# ISL.net
KiCad netlist of a schematic drawn in EasyEDA
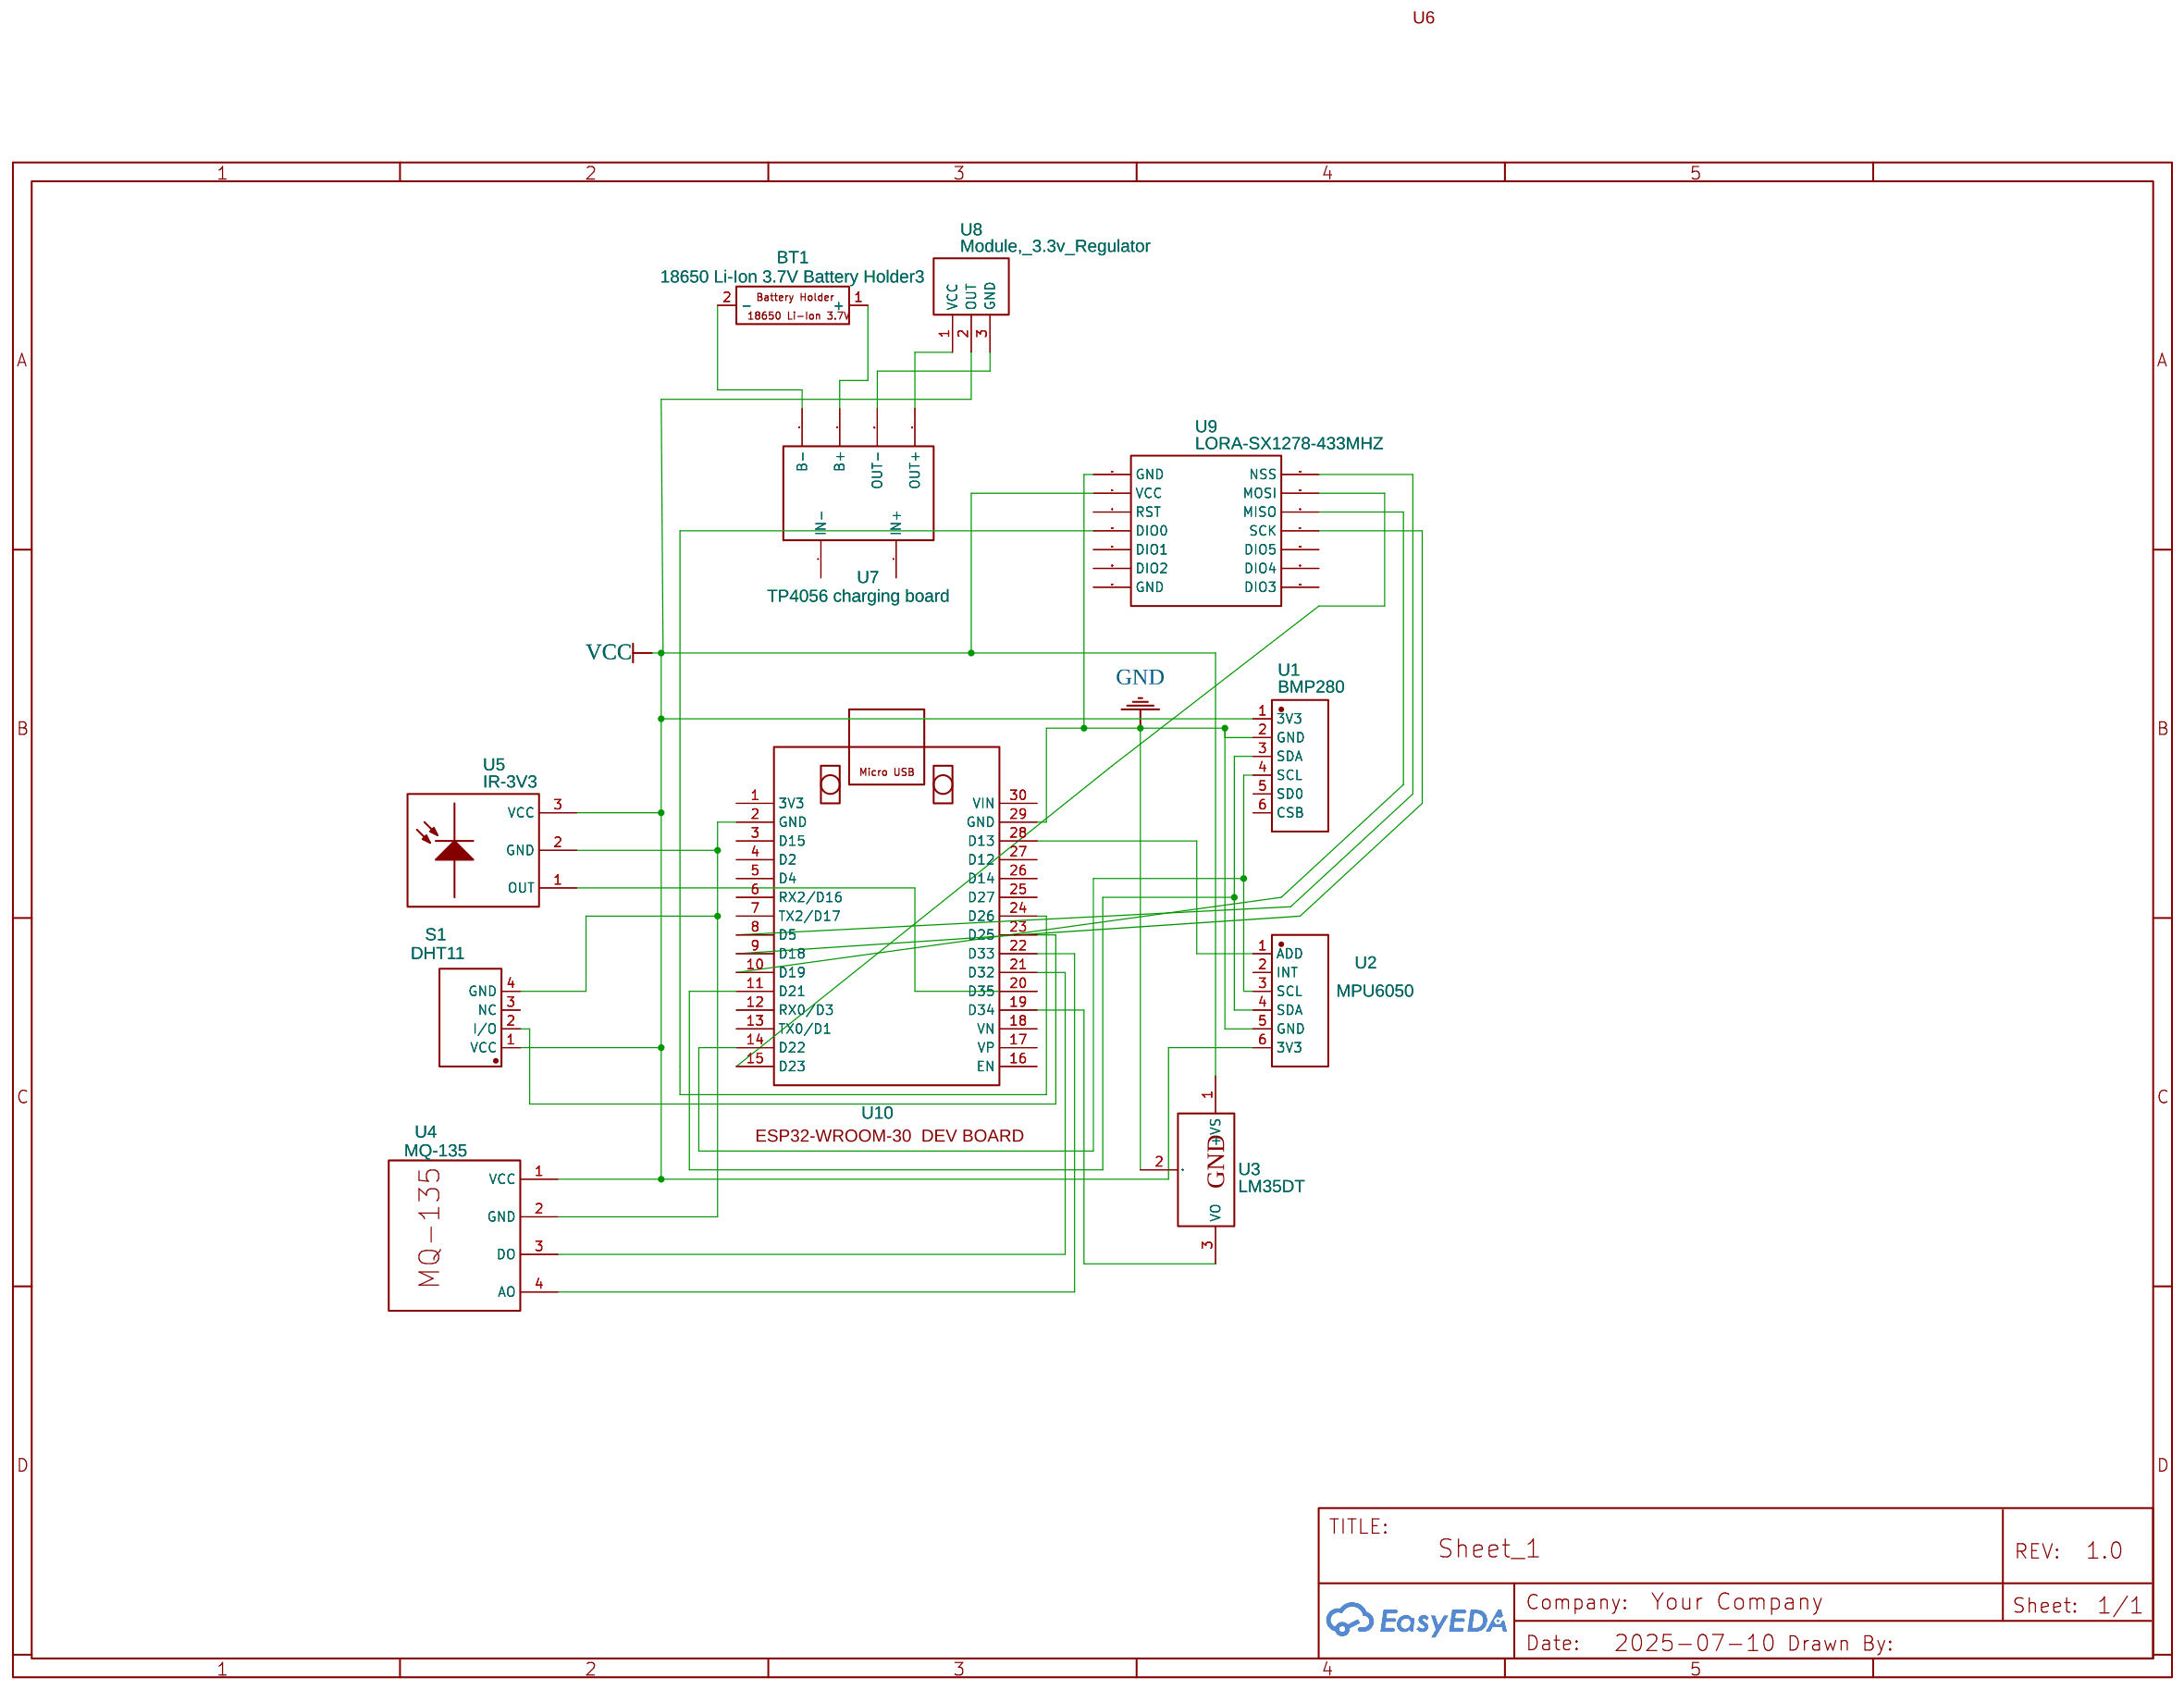
[diagram p0: Sheet_1]
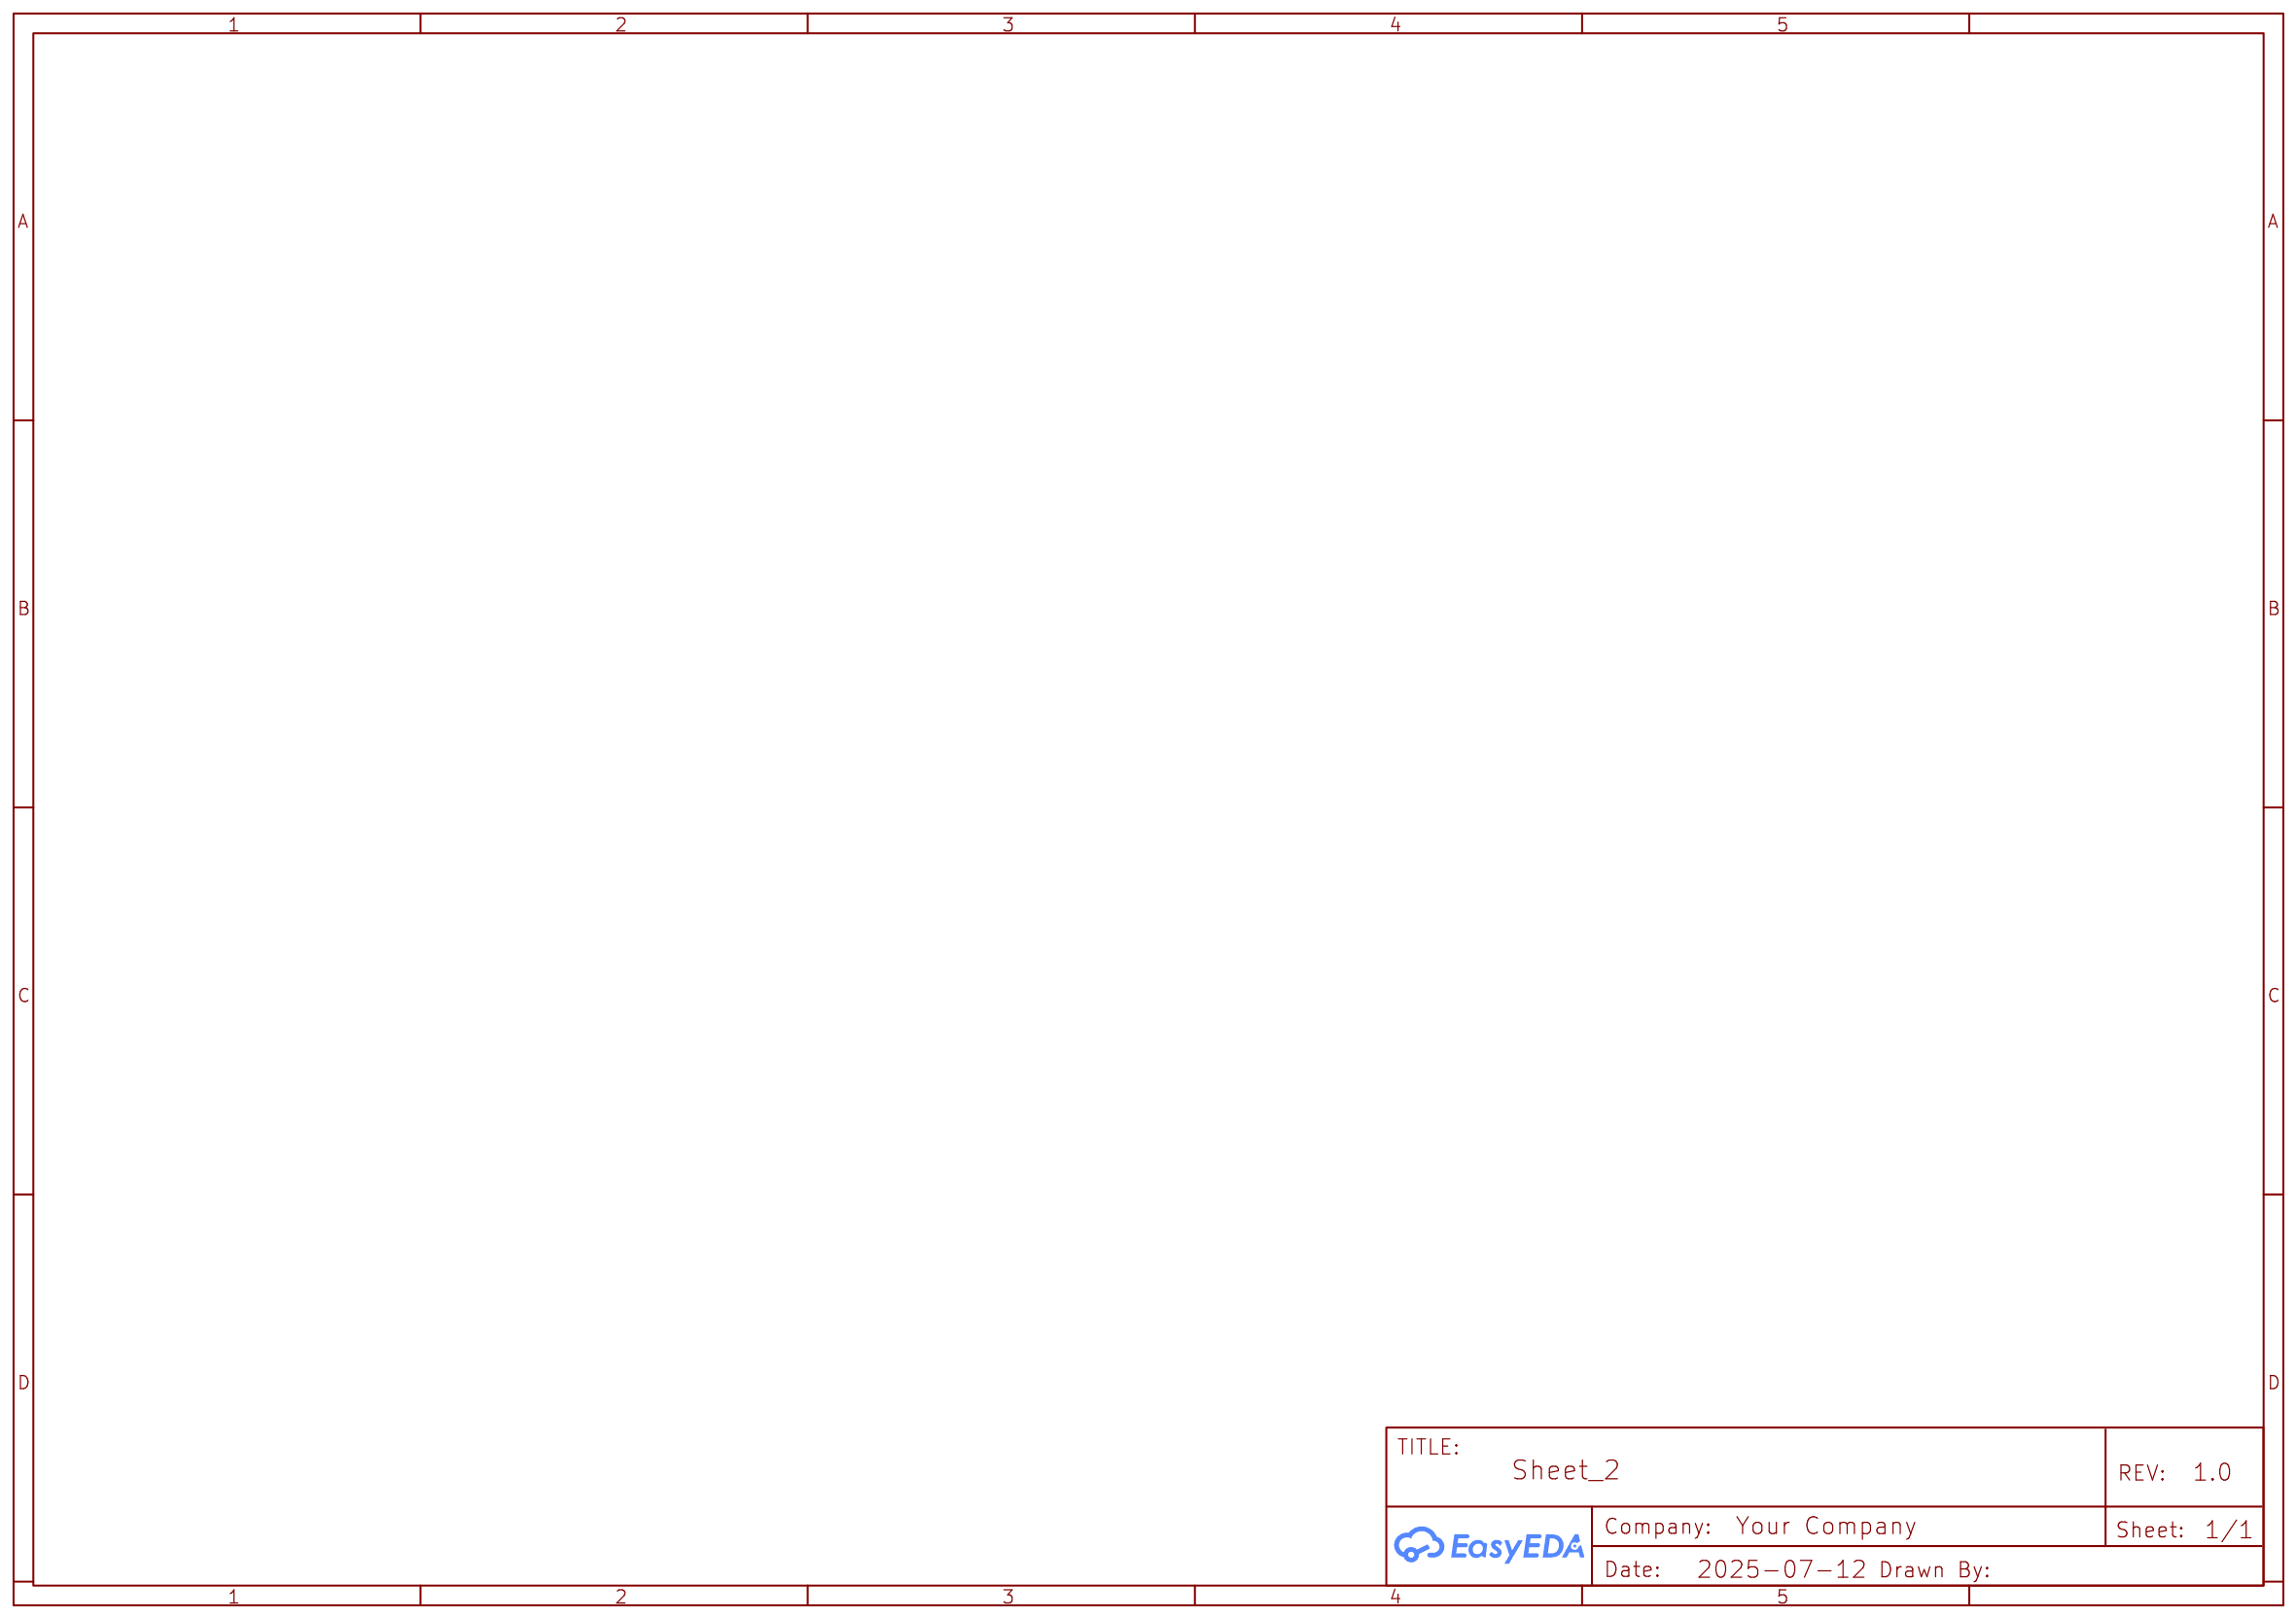
[diagram p1: Sheet_2]

(export (version "E")
  (design (tool "Eeschema 10.0.6"))
  (components
    (comp (ref "BT1")
      (value "18650 Li-Ion 3.7V Battery Holder3")
      (fields (field (name "Manufacturer Part") "18650_Li_BT_3P7V") (field (name "Manufacturer") "Smartcube"))
      (libsource (lib "") (part "18650 Li-Ion 3.7V Battery Holder3"))
    )
    (comp (ref "S1")
      (value "DHT11")
      (fields (field (name "Manufacturer") "AOSONG"))
      (libsource (lib "") (part "DHT11_C87032"))
    )
    (comp (ref "U1") (value "BMP280") (libsource (lib "") (part "BMP280_C9900132626")))
    (comp (ref "U2")
      (value "MPU6050")
      (fields (field (name "Manufacturer Part") "MPU6050-TH"))
      (libsource (lib "") (part "MPU6050-TH"))
    )
    (comp (ref "U3")
      (value "LM35DT")
      (fields (field (name "Manufacturer Part") "LM35DT/NOPB") (field (name "Manufacturer") "TI(德州仪器)"))
      (libsource (lib "") (part "LM35DT"))
    )
    (comp (ref "U4") (value "MQ-135") (libsource (lib "") (part "MQ-135 SENSOR COPY")))
    (comp (ref "U5") (value "IR-3V3") (libsource (lib "") (part "IR-3V3")))
    (comp (ref "U7") (value "TP4056 charging board") (libsource (lib "") (part "TP4056 charging board")))
    (comp (ref "U8")
      (value "Module,_3.3v_Regulator")
      (fields (field (name "Manufacturer Part") "Module, 3.3v Regulator"))
      (libsource (lib "") (part "Module,_3.3v_Regulator"))
    )
    (comp (ref "U9")
      (value "LORA-SX1278-433MHZ")
      (fields (field (name "Manufacturer Part") "New SchematicLib"))
      (libsource (lib "") (part "LORA-SX1278-433MHZ"))
    )
    (comp (ref "U10") (value "ESP32-WROOM-30  DEVB") (libsource (lib "") (part "ESP32-WROOM-30  DEVB")))
  )
  (nets
    (net (code "1") (name "GND") (class "Default")
      (node (ref "U1") (pin "2") (pinfunction "GND_2") (pintype "unspecified"))
      (node (ref "U10") (pin "29") (pinfunction "GND_29") (pintype "unspecified"))
      (node (ref "U2") (pin "5") (pinfunction "GND_5") (pintype "unspecified"))
      (node (ref "U3") (pin "2") (pinfunction "GND_2") (pintype "passive"))
      (node (ref "U9") (pin "GND") (pinfunction "GND_GND") (pintype "unspecified"))
    )
    (net (code "2") (name "Net-(BT1-+)") (class "Default")
      (node (ref "BT1") (pin "1") (pinfunction "+_1") (pintype "passive"))
      (node (ref "U7") (pin "B+") (pinfunction "B+_B+") (pintype "unspecified"))
    )
    (net (code "3") (name "Net-(BT1--)") (class "Default")
      (node (ref "BT1") (pin "2") (pinfunction "-_2") (pintype "passive"))
      (node (ref "U7") (pin "B-") (pinfunction "B-_B-") (pintype "unspecified"))
    )
    (net (code "4") (name "Net-(S1-GND)") (class "Default")
      (node (ref "S1") (pin "4") (pinfunction "GND_4") (pintype "unspecified"))
      (node (ref "U10") (pin "2") (pinfunction "GND_2") (pintype "unspecified"))
      (node (ref "U4") (pin "2") (pinfunction "GND_2") (pintype "unspecified"))
      (node (ref "U5") (pin "2") (pinfunction "GND_2") (pintype "input"))
    )
    (net (code "5") (name "Net-(S1-I{slash}O)") (class "Default")
      (node (ref "S1") (pin "2") (pinfunction "I/O_2") (pintype "unspecified"))
      (node (ref "U10") (pin "23") (pinfunction "D25_23") (pintype "unspecified"))
    )
    (net (code "6") (name "Net-(U1-SCL)") (class "Default")
      (node (ref "U1") (pin "4") (pinfunction "SCL_4") (pintype "unspecified"))
      (node (ref "U10") (pin "14") (pinfunction "D22_14") (pintype "unspecified"))
      (node (ref "U2") (pin "3") (pinfunction "SCL_3") (pintype "unspecified"))
    )
    (net (code "7") (name "Net-(U1-SDA)") (class "Default")
      (node (ref "U1") (pin "3") (pinfunction "SDA_3") (pintype "unspecified"))
      (node (ref "U10") (pin "11") (pinfunction "D21_11") (pintype "unspecified"))
      (node (ref "U2") (pin "4") (pinfunction "SDA_4") (pintype "unspecified"))
    )
    (net (code "8") (name "Net-(U8-GND)") (class "Default")
      (node (ref "U7") (pin "OUT-") (pinfunction "OUT-_OUT-") (pintype "unspecified"))
      (node (ref "U8") (pin "3") (pinfunction "GND_3") (pintype "unspecified"))
    )
    (net (code "9") (name "Net-(U8-VCC)") (class "Default")
      (node (ref "U7") (pin "OUT+") (pinfunction "OUT+_OUT+") (pintype "unspecified"))
      (node (ref "U8") (pin "1") (pinfunction "VCC_1") (pintype "unspecified"))
    )
    (net (code "10") (name "Net-(U10-D5)") (class "Default")
      (node (ref "U10") (pin "8") (pinfunction "D5_8") (pintype "unspecified"))
      (node (ref "U9") (pin "NSS") (pinfunction "NSS_NSS") (pintype "unspecified"))
    )
    (net (code "11") (name "Net-(U10-D13)") (class "Default")
      (node (ref "U10") (pin "28") (pinfunction "D13_28") (pintype "unspecified"))
      (node (ref "U2") (pin "1") (pinfunction "ADD_1") (pintype "unspecified"))
    )
    (net (code "12") (name "Net-(U10-D18)") (class "Default")
      (node (ref "U10") (pin "9") (pinfunction "D18_9") (pintype "unspecified"))
      (node (ref "U9") (pin "SCK") (pinfunction "SCK_SCK") (pintype "unspecified"))
    )
    (net (code "13") (name "Net-(U10-D19)") (class "Default")
      (node (ref "U10") (pin "10") (pinfunction "D19_10") (pintype "unspecified"))
      (node (ref "U9") (pin "MISO") (pinfunction "MISO_MISO") (pintype "unspecified"))
    )
    (net (code "14") (name "Net-(U10-D23)") (class "Default")
      (node (ref "U10") (pin "15") (pinfunction "D23_15") (pintype "unspecified"))
      (node (ref "U9") (pin "MOSI") (pinfunction "MOSI_MOSI") (pintype "unspecified"))
    )
    (net (code "15") (name "Net-(U10-D26)") (class "Default")
      (node (ref "U10") (pin "24") (pinfunction "D26_24") (pintype "unspecified"))
      (node (ref "U9") (pin "DIO0") (pinfunction "DIO0_DIO0") (pintype "unspecified"))
    )
    (net (code "16") (name "Net-(U10-D32)") (class "Default")
      (node (ref "U10") (pin "21") (pinfunction "D32_21") (pintype "unspecified"))
      (node (ref "U4") (pin "3") (pinfunction "DO_3") (pintype "unspecified"))
    )
    (net (code "17") (name "Net-(U10-D33)") (class "Default")
      (node (ref "U10") (pin "22") (pinfunction "D33_22") (pintype "unspecified"))
      (node (ref "U4") (pin "4") (pinfunction "AO_4") (pintype "unspecified"))
    )
    (net (code "18") (name "Net-(U10-D34)") (class "Default")
      (node (ref "U10") (pin "19") (pinfunction "D34_19") (pintype "unspecified"))
      (node (ref "U3") (pin "3") (pinfunction "VO_3") (pintype "output"))
    )
    (net (code "19") (name "Net-(U10-D35)") (class "Default")
      (node (ref "U10") (pin "20") (pinfunction "D35_20") (pintype "unspecified"))
      (node (ref "U5") (pin "1") (pinfunction "OUT_1") (pintype "input"))
    )
    (net (code "20") (name "VCC") (class "Default")
      (node (ref "S1") (pin "1") (pinfunction "VCC_1") (pintype "unspecified"))
      (node (ref "U1") (pin "1") (pinfunction "3V3_1") (pintype "unspecified"))
      (node (ref "U2") (pin "6") (pinfunction "3V3_6") (pintype "unspecified"))
      (node (ref "U3") (pin "1") (pinfunction "+VS_1") (pintype "unspecified"))
      (node (ref "U4") (pin "1") (pinfunction "VCC_1") (pintype "unspecified"))
      (node (ref "U5") (pin "3") (pinfunction "VCC_3") (pintype "input"))
      (node (ref "U8") (pin "2") (pinfunction "OUT_2") (pintype "unspecified"))
      (node (ref "U9") (pin "VCC") (pinfunction "VCC_VCC") (pintype "unspecified"))
    )
    (net (code "21") (name "unconnected-(S1-NC-Pad3)") (class "Default")
      (node (ref "S1") (pin "3") (pinfunction "NC_3") (pintype "unspecified"))
    )
    (net (code "22") (name "unconnected-(U1-CSB-Pad6)") (class "Default")
      (node (ref "U1") (pin "6") (pinfunction "CSB_6") (pintype "unspecified"))
    )
    (net (code "23") (name "unconnected-(U1-SD0-Pad5)") (class "Default")
      (node (ref "U1") (pin "5") (pinfunction "SD0_5") (pintype "unspecified"))
    )
    (net (code "24") (name "unconnected-(U2-INT-Pad2)") (class "Default")
      (node (ref "U2") (pin "2") (pinfunction "INT_2") (pintype "unspecified"))
    )
    (net (code "25") (name "unconnected-(U7-PadIN+)") (class "Default")
      (node (ref "U7") (pin "IN+") (pinfunction "IN+_IN+") (pintype "unspecified"))
    )
    (net (code "26") (name "unconnected-(U7-PadIN-)") (class "Default")
      (node (ref "U7") (pin "IN-") (pinfunction "IN-_IN-") (pintype "unspecified"))
    )
    (net (code "27") (name "unconnected-(U9-PadDIO1)") (class "Default")
      (node (ref "U9") (pin "DIO1") (pinfunction "DIO1_DIO1") (pintype "unspecified"))
    )
    (net (code "28") (name "unconnected-(U9-PadDIO2)") (class "Default")
      (node (ref "U9") (pin "DIO2") (pinfunction "DIO2_DIO2") (pintype "unspecified"))
    )
    (net (code "29") (name "unconnected-(U9-PadDIO3)") (class "Default")
      (node (ref "U9") (pin "DIO3") (pinfunction "DIO3_DIO3") (pintype "unspecified"))
    )
    (net (code "30") (name "unconnected-(U9-PadDIO4)") (class "Default")
      (node (ref "U9") (pin "DIO4") (pinfunction "DIO4_DIO4") (pintype "unspecified"))
    )
    (net (code "31") (name "unconnected-(U9-PadDIO5)") (class "Default")
      (node (ref "U9") (pin "DIO5") (pinfunction "DIO5_DIO5") (pintype "unspecified"))
    )
    (net (code "32") (name "unconnected-(U9-PadGND)") (class "Default")
      (node (ref "U9") (pin "GND") (pinfunction "GND_GND") (pintype "unspecified"))
    )
    (net (code "33") (name "unconnected-(U9-PadRST)") (class "Default")
      (node (ref "U9") (pin "RST") (pinfunction "RST_RST") (pintype "unspecified"))
    )
    (net (code "34") (name "unconnected-(U10-3V3-Pad1)") (class "Default")
      (node (ref "U10") (pin "1") (pinfunction "3V3_1") (pintype "unspecified"))
    )
    (net (code "35") (name "unconnected-(U10-D2-Pad4)") (class "Default")
      (node (ref "U10") (pin "4") (pinfunction "D2_4") (pintype "unspecified"))
    )
    (net (code "36") (name "unconnected-(U10-D4-Pad5)") (class "Default")
      (node (ref "U10") (pin "5") (pinfunction "D4_5") (pintype "unspecified"))
    )
    (net (code "37") (name "unconnected-(U10-D12-Pad27)") (class "Default")
      (node (ref "U10") (pin "27") (pinfunction "D12_27") (pintype "unspecified"))
    )
    (net (code "38") (name "unconnected-(U10-D14-Pad26)") (class "Default")
      (node (ref "U10") (pin "26") (pinfunction "D14_26") (pintype "unspecified"))
    )
    (net (code "39") (name "unconnected-(U10-D15-Pad3)") (class "Default")
      (node (ref "U10") (pin "3") (pinfunction "D15_3") (pintype "unspecified"))
    )
    (net (code "40") (name "unconnected-(U10-D27-Pad25)") (class "Default")
      (node (ref "U10") (pin "25") (pinfunction "D27_25") (pintype "unspecified"))
    )
    (net (code "41") (name "unconnected-(U10-EN-Pad16)") (class "Default")
      (node (ref "U10") (pin "16") (pinfunction "EN_16") (pintype "unspecified"))
    )
    (net (code "42") (name "unconnected-(U10-RX0{slash}D3-Pad12)") (class "Default")
      (node (ref "U10") (pin "12") (pinfunction "RX0/D3_12") (pintype "unspecified"))
    )
    (net (code "43") (name "unconnected-(U10-RX2{slash}D16-Pad6)") (class "Default")
      (node (ref "U10") (pin "6") (pinfunction "RX2/D16_6") (pintype "unspecified"))
    )
    (net (code "44") (name "unconnected-(U10-TX0{slash}D1-Pad13)") (class "Default")
      (node (ref "U10") (pin "13") (pinfunction "TX0/D1_13") (pintype "unspecified"))
    )
    (net (code "45") (name "unconnected-(U10-TX2{slash}D17-Pad7)") (class "Default")
      (node (ref "U10") (pin "7") (pinfunction "TX2/D17_7") (pintype "unspecified"))
    )
    (net (code "46") (name "unconnected-(U10-VIN-Pad30)") (class "Default")
      (node (ref "U10") (pin "30") (pinfunction "VIN_30") (pintype "unspecified"))
    )
    (net (code "47") (name "unconnected-(U10-VN-Pad18)") (class "Default")
      (node (ref "U10") (pin "18") (pinfunction "VN_18") (pintype "unspecified"))
    )
    (net (code "48") (name "unconnected-(U10-VP-Pad17)") (class "Default")
      (node (ref "U10") (pin "17") (pinfunction "VP_17") (pintype "unspecified"))
    )
  )
)
